# sensor_de_aplausos.net
KiCad netlist of a schematic drawn in EAGLE
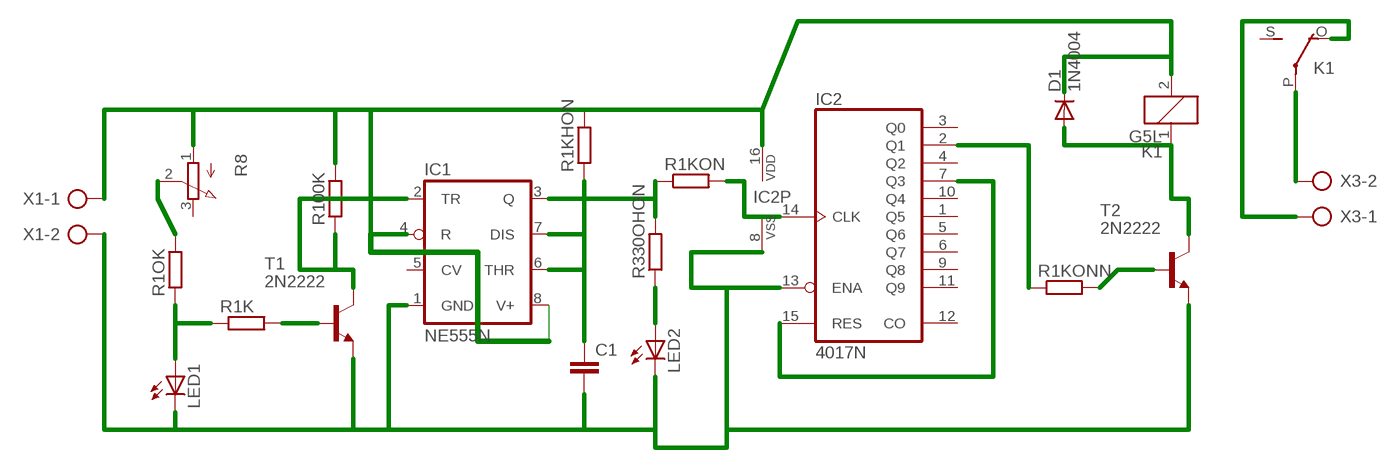
[diagram p0: schematic, sheet 1]

(export (version "E")
  (design (tool "Eeschema 10.0.6"))
  (components
    (comp (ref "C1")
      (value "C5/5")
      (footprint "eagle-import:C5B5")
      (libsource (lib "eagle-import") (part "C5/5"))
    )
    (comp (ref "D1")
      (value "1N4004")
      (footprint "eagle-import:DO41-10")
      (libsource (lib "eagle-import") (part "1N4004"))
    )
    (comp (ref "IC1")
      (value "NE555N")
      (footprint "eagle-import:DIL08")
      (libsource (lib "eagle-import") (part "555NNE"))
    )
    (comp (ref "IC2")
      (value "4017N")
      (footprint "eagle-import:DIL16")
      (libsource (lib "eagle-import") (part "4017N"))
    )
    (comp (ref "K1")
      (value "G5L")
      (footprint "eagle-import:G5LE")
      (libsource (lib "eagle-import") (part "G5L"))
    )
    (comp (ref "LED1")
      (value "LED5MM")
      (footprint "eagle-import:LED5MM")
      (libsource (lib "eagle-import") (part "LED5MM"))
    )
    (comp (ref "LED2")
      (value "LED5MM")
      (footprint "eagle-import:LED5MM")
      (libsource (lib "eagle-import") (part "LED5MM"))
    )
    (comp (ref "R1K")
      (value "R-EU_0207/12")
      (footprint "eagle-import:0207_12")
      (libsource (lib "eagle-import") (part "R-EU_0207/12"))
    )
    (comp (ref "R1KHON")
      (value "R-EU_0207/12")
      (footprint "eagle-import:0207_12")
      (libsource (lib "eagle-import") (part "R-EU_0207/12"))
    )
    (comp (ref "R1KON")
      (value "R-EU_0207/12")
      (footprint "eagle-import:0207_12")
      (libsource (lib "eagle-import") (part "R-EU_0207/12"))
    )
    (comp (ref "R1KONN")
      (value "R-EU_0207/12")
      (footprint "eagle-import:0207_12")
      (libsource (lib "eagle-import") (part "R-EU_0207/12"))
    )
    (comp (ref "R1OK")
      (value "R-EU_0207/12")
      (footprint "eagle-import:0207_12")
      (libsource (lib "eagle-import") (part "R-EU_0207/12"))
    )
    (comp (ref "R8")
      (value "3RP/1610N")
      (footprint "eagle-import:3RP_1610N")
      (libsource (lib "eagle-import") (part "3RP/1610N"))
    )
    (comp (ref "R100K")
      (value "R-EU_0207/12")
      (footprint "eagle-import:0207_12")
      (libsource (lib "eagle-import") (part "R-EU_0207/12"))
    )
    (comp (ref "R330OHON")
      (value "R-EU_0207/12")
      (footprint "eagle-import:0207_12")
      (libsource (lib "eagle-import") (part "R-EU_0207/12"))
    )
    (comp (ref "T1")
      (value "2N2222")
      (footprint "eagle-import:TO18")
      (libsource (lib "eagle-import") (part "2N2222"))
    )
    (comp (ref "T2")
      (value "2N2222")
      (footprint "eagle-import:TO18")
      (libsource (lib "eagle-import") (part "2N2222"))
    )
    (comp (ref "X1")
      (value "AK300/2")
      (footprint "eagle-import:AK300_2")
      (libsource (lib "eagle-import") (part "AK300/2"))
    )
    (comp (ref "X3")
      (value "AK300/2")
      (footprint "eagle-import:AK300_2")
      (libsource (lib "eagle-import") (part "AK300/2"))
    )
  )
  (nets
    (net (code "1") (name "Net-(IC1-DIS)") (class "Default")
      (node (ref "C1") (pin "1") (pinfunction "1_1") (pintype "passive"))
      (node (ref "IC1") (pin "6") (pinfunction "THR_6") (pintype "input"))
      (node (ref "IC1") (pin "7") (pinfunction "DIS_7") (pintype "input"))
      (node (ref "R1KHON") (pin "1") (pinfunction "1_1") (pintype "passive"))
    )
    (net (code "2") (name "Net-(IC1-GND)") (class "Default")
      (node (ref "C1") (pin "2") (pinfunction "2_2") (pintype "passive"))
      (node (ref "IC1") (pin "1") (pinfunction "GND_1") (pintype "power_in"))
      (node (ref "IC2") (pin "13") (pinfunction "ENA_13") (pintype "input"))
      (node (ref "IC2") (pin "8") (pinfunction "VSS_8") (pintype "power_in"))
      (node (ref "LED1") (pin "K") (pinfunction "C_K") (pintype "passive"))
      (node (ref "LED2") (pin "K") (pinfunction "C_K") (pintype "passive"))
      (node (ref "T1") (pin "1") (pinfunction "E_1") (pintype "passive"))
      (node (ref "T2") (pin "1") (pinfunction "E_1") (pintype "passive"))
      (node (ref "X1") (pin "2") (pinfunction "KL_2") (pintype "passive"))
    )
    (net (code "3") (name "Net-(IC1-Q)") (class "Default")
      (node (ref "IC1") (pin "3") (pinfunction "Q_3") (pintype "output"))
      (node (ref "R1KON") (pin "1") (pinfunction "1_1") (pintype "passive"))
      (node (ref "R330OHON") (pin "2") (pinfunction "2_2") (pintype "passive"))
    )
    (net (code "4") (name "Net-(IC1-R)") (class "Default")
      (node (ref "D1") (pin "C") (pinfunction "C_C") (pintype "passive"))
      (node (ref "IC1") (pin "4") (pinfunction "R_4") (pintype "input"))
      (node (ref "IC1") (pin "8") (pinfunction "V+_8") (pintype "power_in"))
      (node (ref "IC2") (pin "16") (pinfunction "VDD_16") (pintype "power_in"))
      (node (ref "K1") (pin "2") (pinfunction "2_2") (pintype "passive"))
      (node (ref "R100K") (pin "2") (pinfunction "2_2") (pintype "passive"))
      (node (ref "R1KHON") (pin "2") (pinfunction "2_2") (pintype "passive"))
      (node (ref "R8") (pin "1") (pinfunction "A_1") (pintype "passive"))
      (node (ref "X1") (pin "1") (pinfunction "KL_1") (pintype "passive"))
    )
    (net (code "5") (name "Net-(IC1-TR)") (class "Default")
      (node (ref "IC1") (pin "2") (pinfunction "TR_2") (pintype "input"))
      (node (ref "R100K") (pin "1") (pinfunction "1_1") (pintype "passive"))
      (node (ref "T1") (pin "3") (pinfunction "C_3") (pintype "passive"))
    )
    (net (code "6") (name "Net-(IC2A-CLK)") (class "Default")
      (node (ref "IC2") (pin "14") (pinfunction "CLK_14") (pintype "input"))
      (node (ref "R1KON") (pin "2") (pinfunction "2_2") (pintype "passive"))
    )
    (net (code "7") (name "Net-(IC2A-Q1)") (class "Default")
      (node (ref "IC2") (pin "2") (pinfunction "Q1_2") (pintype "output"))
      (node (ref "R1KONN") (pin "1") (pinfunction "1_1") (pintype "passive"))
    )
    (net (code "8") (name "Net-(IC2A-Q3)") (class "Default")
      (node (ref "IC2") (pin "15") (pinfunction "RES_15") (pintype "input"))
      (node (ref "IC2") (pin "7") (pinfunction "Q3_7") (pintype "output"))
    )
    (net (code "9") (name "Net-(LED1-PadA)") (class "Default")
      (node (ref "LED1") (pin "A") (pinfunction "A_A") (pintype "passive"))
      (node (ref "R1K") (pin "1") (pinfunction "1_1") (pintype "passive"))
      (node (ref "R1OK") (pin "1") (pinfunction "1_1") (pintype "passive"))
    )
    (net (code "10") (name "Net-(LED2-PadA)") (class "Default")
      (node (ref "LED2") (pin "A") (pinfunction "A_A") (pintype "passive"))
      (node (ref "R330OHON") (pin "1") (pinfunction "1_1") (pintype "passive"))
    )
    (net (code "11") (name "Net-(R8-S)") (class "Default")
      (node (ref "R1OK") (pin "2") (pinfunction "2_2") (pintype "passive"))
      (node (ref "R8") (pin "2") (pinfunction "S_2") (pintype "passive"))
    )
    (net (code "12") (name "Net-(T1-B)") (class "Default")
      (node (ref "R1K") (pin "2") (pinfunction "2_2") (pintype "passive"))
      (node (ref "T1") (pin "2") (pinfunction "B_2") (pintype "passive"))
    )
    (net (code "13") (name "Net-(T2-B)") (class "Default")
      (node (ref "R1KONN") (pin "2") (pinfunction "2_2") (pintype "passive"))
      (node (ref "T2") (pin "2") (pinfunction "B_2") (pintype "passive"))
    )
    (net (code "14") (name "Net-(T2-C)") (class "Default")
      (node (ref "D1") (pin "A") (pinfunction "A_A") (pintype "passive"))
      (node (ref "K1") (pin "1") (pinfunction "1_1") (pintype "passive"))
      (node (ref "T2") (pin "3") (pinfunction "C_3") (pintype "passive"))
    )
    (net (code "15") (name "Net-(X3A-KL)") (class "Default")
      (node (ref "K1") (pin "O") (pinfunction "O_O") (pintype "passive"))
      (node (ref "X3") (pin "1") (pinfunction "KL_1") (pintype "passive"))
    )
    (net (code "16") (name "Net-(X3B-KL)") (class "Default")
      (node (ref "K1") (pin "P") (pinfunction "P_P") (pintype "passive"))
      (node (ref "X3") (pin "2") (pinfunction "KL_2") (pintype "passive"))
    )
    (net (code "17") (name "unconnected-(IC1-CV-Pad5)") (class "Default")
      (node (ref "IC1") (pin "5") (pinfunction "CV_5") (pintype "input"))
    )
    (net (code "18") (name "unconnected-(IC2A-CO-Pad12)") (class "Default")
      (node (ref "IC2") (pin "12") (pinfunction "CO_12") (pintype "output"))
    )
    (net (code "19") (name "unconnected-(IC2A-Q0-Pad3)") (class "Default")
      (node (ref "IC2") (pin "3") (pinfunction "Q0_3") (pintype "output"))
    )
    (net (code "20") (name "unconnected-(IC2A-Q2-Pad4)") (class "Default")
      (node (ref "IC2") (pin "4") (pinfunction "Q2_4") (pintype "output"))
    )
    (net (code "21") (name "unconnected-(IC2A-Q4-Pad10)") (class "Default")
      (node (ref "IC2") (pin "10") (pinfunction "Q4_10") (pintype "output"))
    )
    (net (code "22") (name "unconnected-(IC2A-Q5-Pad1)") (class "Default")
      (node (ref "IC2") (pin "1") (pinfunction "Q5_1") (pintype "output"))
    )
    (net (code "23") (name "unconnected-(IC2A-Q6-Pad5)") (class "Default")
      (node (ref "IC2") (pin "5") (pinfunction "Q6_5") (pintype "output"))
    )
    (net (code "24") (name "unconnected-(IC2A-Q7-Pad6)") (class "Default")
      (node (ref "IC2") (pin "6") (pinfunction "Q7_6") (pintype "output"))
    )
    (net (code "25") (name "unconnected-(IC2A-Q8-Pad9)") (class "Default")
      (node (ref "IC2") (pin "9") (pinfunction "Q8_9") (pintype "output"))
    )
    (net (code "26") (name "unconnected-(IC2A-Q9-Pad11)") (class "Default")
      (node (ref "IC2") (pin "11") (pinfunction "Q9_11") (pintype "output"))
    )
    (net (code "27") (name "unconnected-(K1-PadS)") (class "Default")
      (node (ref "K1") (pin "S") (pinfunction "S_S") (pintype "passive"))
    )
    (net (code "28") (name "unconnected-(R8-E-Pad3)") (class "Default")
      (node (ref "R8") (pin "3") (pinfunction "E_3") (pintype "passive"))
    )
  )
)
